# Components.net
KiCad netlist of a schematic drawn in Altium Designer
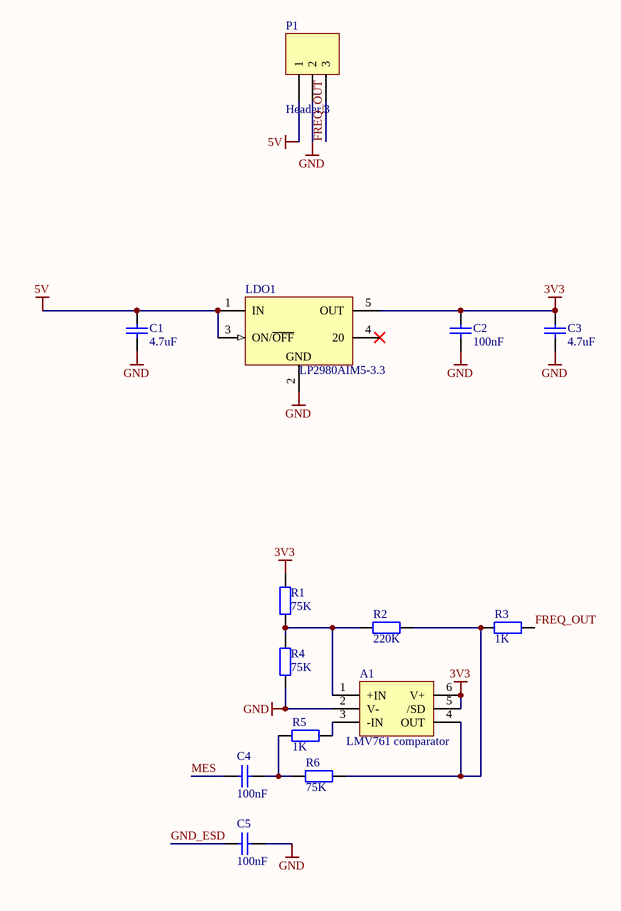
[diagram p0: Components.SchDoc]

(export (version "E")
  (design (tool "Eeschema 10.0.6"))
  (components
    (comp (ref "A1")
      (value "LMV761 comparator")
      (footprint "ANALOG_SOT23-6")
      (description "LMV761  precision comparator")
      (libsource (lib "Analog") (part "LMV761"))
    )
    (comp (ref "C1")
      (value "4.7uF")
      (footprint "FP_0603_CAP_080")
      (description "Capacitor")
      (libsource (lib "Miscellaneous Devices") (part "Cap"))
    )
    (comp (ref "C2")
      (value "100nF")
      (footprint "FP_0603_CAP_080")
      (description "Capacitor")
      (libsource (lib "Miscellaneous Devices") (part "Cap"))
    )
    (comp (ref "C3")
      (value "4.7uF")
      (footprint "FP_0603_CAP_080")
      (description "Capacitor")
      (libsource (lib "Miscellaneous Devices") (part "Cap"))
    )
    (comp (ref "C4")
      (value "100nF")
      (footprint "FP_0603_CAP_080")
      (description "Capacitor")
      (libsource (lib "Miscellaneous Devices") (part "Cap"))
    )
    (comp (ref "C5")
      (value "100nF")
      (footprint "FP_0603_CAP_080")
      (description "Capacitor")
      (libsource (lib "Miscellaneous Devices") (part "Cap"))
    )
    (comp (ref "LDO1")
      (value "LP2980AIM5-3.3")
      (footprint "SUPPLY_SOT23-5")
      (description "Micropower 50 mA Ultra Low-Dropout Regulator In SOT-23 and micro SMD Packages")
      (libsource (lib "Supply") (part "LP2980IM5-3.8"))
    )
    (comp (ref "P1")
      (value "Header 3")
      (footprint "HDR1X3")
      (description "Header, 3-Pin")
      (fields (field (name "PUBLISHER") "Altium Limited"))
      (libsource (lib "Miscellaneous Connectors") (part "Header 3"))
    )
    (comp (ref "R1")
      (value "75K")
      (footprint "FP_0603_RES")
      (description "Resistor")
      (libsource (lib "") (part "Res3_1"))
    )
    (comp (ref "R2")
      (value "220K")
      (footprint "FP_0603_RES")
      (description "Resistor")
      (libsource (lib "Miscellaneous Devices") (part "Res3"))
    )
    (comp (ref "R3")
      (value "1K")
      (footprint "FP_0603_RES")
      (description "Resistor")
      (libsource (lib "Miscellaneous Devices") (part "Res3"))
    )
    (comp (ref "R4")
      (value "75K")
      (footprint "FP_0603_RES")
      (description "Resistor")
      (libsource (lib "") (part "Res3_1"))
    )
    (comp (ref "R5")
      (value "1K")
      (footprint "FP_0603_RES")
      (description "Resistor")
      (libsource (lib "Miscellaneous Devices") (part "Res3"))
    )
    (comp (ref "R6")
      (value "75K")
      (footprint "FP_0603_RES")
      (description "Resistor")
      (libsource (lib "Miscellaneous Devices") (part "Res3"))
    )
  )
  (nets
    (net (code "1") (name "/FREQ_OUT") (class "Default")
      (node (ref "P1") (pin "3") (pinfunction "3_3") (pintype "passive"))
      (node (ref "R3") (pin "2") (pinfunction "2_2") (pintype "passive"))
    )
    (net (code "2") (name "/GND_ESD") (class "Default")
      (node (ref "C5") (pin "1") (pinfunction "1_1") (pintype "passive"))
    )
    (net (code "3") (name "/MES") (class "Default")
      (node (ref "C4") (pin "1") (pinfunction "1_1") (pintype "passive"))
    )
    (net (code "4") (name "3V3") (class "Default")
      (node (ref "A1") (pin "5") (pinfunction "/SD_5") (pintype "passive"))
      (node (ref "A1") (pin "6") (pinfunction "V+_6") (pintype "passive"))
      (node (ref "C2") (pin "2") (pinfunction "2_2") (pintype "passive"))
      (node (ref "C3") (pin "2") (pinfunction "2_2") (pintype "passive"))
      (node (ref "LDO1") (pin "5") (pinfunction "OUT_5") (pintype "passive"))
      (node (ref "R1") (pin "1") (pinfunction "1_1") (pintype "passive"))
    )
    (net (code "5") (name "5V") (class "Default")
      (node (ref "C1") (pin "2") (pinfunction "2_2") (pintype "passive"))
      (node (ref "LDO1") (pin "1") (pinfunction "IN_1") (pintype "passive"))
      (node (ref "LDO1") (pin "3") (pinfunction "ON/~{OFF}_3") (pintype "input"))
      (node (ref "P1") (pin "1") (pinfunction "1_1") (pintype "passive"))
    )
    (net (code "6") (name "GND") (class "Default")
      (node (ref "A1") (pin "2") (pinfunction "V-_2") (pintype "passive"))
      (node (ref "C1") (pin "1") (pinfunction "1_1") (pintype "passive"))
      (node (ref "C2") (pin "1") (pinfunction "1_1") (pintype "passive"))
      (node (ref "C3") (pin "1") (pinfunction "1_1") (pintype "passive"))
      (node (ref "C5") (pin "2") (pinfunction "2_2") (pintype "passive"))
      (node (ref "LDO1") (pin "2") (pinfunction "GND_2") (pintype "passive"))
      (node (ref "P1") (pin "2") (pinfunction "2_2") (pintype "passive"))
      (node (ref "R4") (pin "2") (pinfunction "2_2") (pintype "passive"))
    )
    (net (code "7") (name "Net-(A1-+IN)") (class "Default")
      (node (ref "A1") (pin "1") (pinfunction "+IN_1") (pintype "passive"))
      (node (ref "R1") (pin "2") (pinfunction "2_2") (pintype "passive"))
      (node (ref "R2") (pin "1") (pinfunction "1_1") (pintype "passive"))
      (node (ref "R4") (pin "1") (pinfunction "1_1") (pintype "passive"))
    )
    (net (code "8") (name "Net-(A1--IN)") (class "Default")
      (node (ref "A1") (pin "3") (pinfunction "-IN_3") (pintype "passive"))
      (node (ref "R5") (pin "2") (pinfunction "2_2") (pintype "passive"))
    )
    (net (code "9") (name "Net-(A1-OUT)") (class "Default")
      (node (ref "A1") (pin "4") (pinfunction "OUT_4") (pintype "passive"))
      (node (ref "R2") (pin "2") (pinfunction "2_2") (pintype "passive"))
      (node (ref "R3") (pin "1") (pinfunction "1_1") (pintype "passive"))
      (node (ref "R6") (pin "2") (pinfunction "2_2") (pintype "passive"))
    )
    (net (code "10") (name "Net-(C4-Pad2)") (class "Default")
      (node (ref "C4") (pin "2") (pinfunction "2_2") (pintype "passive"))
      (node (ref "R5") (pin "1") (pinfunction "1_1") (pintype "passive"))
      (node (ref "R6") (pin "1") (pinfunction "1_1") (pintype "passive"))
    )
    (net (code "11") (name "unconnected-(LDO1-20-Pad4)") (class "Default")
      (node (ref "LDO1") (pin "4") (pinfunction "20_4") (pintype "passive+no_connect"))
    )
  )
)
